# ink2.net
KiCad netlist of a schematic drawn in EAGLE
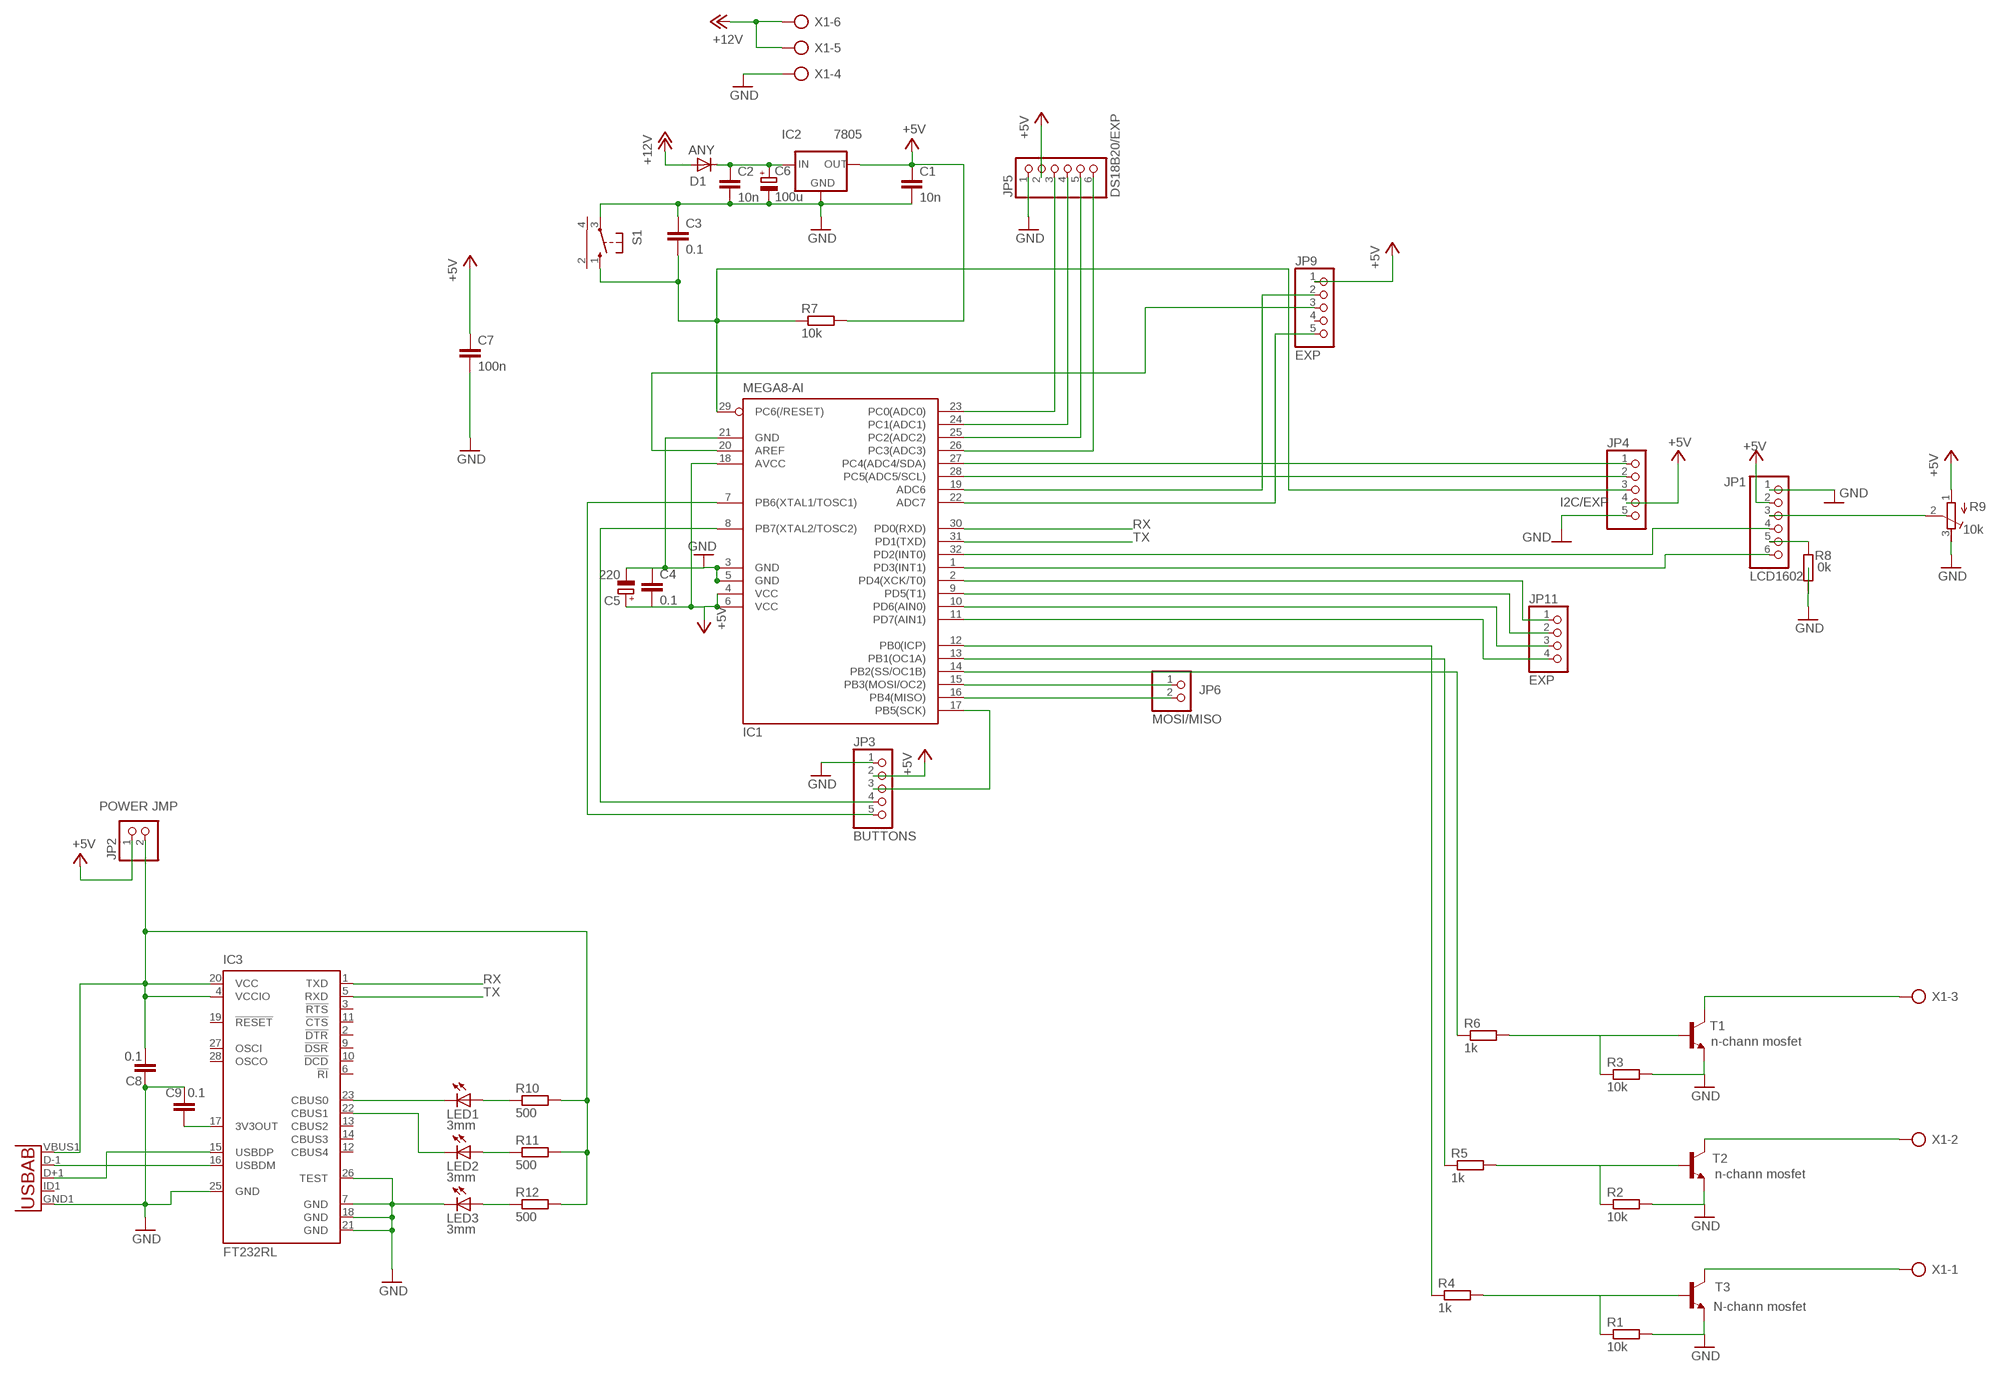
[diagram p0: schematic, sheet 1]

(export (version "E")
  (design (tool "Eeschema 10.0.6"))
  (components
    (comp (ref "ANY")
      (value "D1")
      (footprint "eagle-import:SOD-123_MINI-SMA")
      (libsource (lib "eagle-import") (part "CGRM400-G1"))
    )
    (comp (ref "C1")
      (value "10n")
      (footprint "eagle-import:C1206")
      (libsource (lib "eagle-import") (part "C-EUC1206"))
    )
    (comp (ref "C2")
      (value "10n")
      (footprint "eagle-import:C1206")
      (libsource (lib "eagle-import") (part "C-EUC1206"))
    )
    (comp (ref "C3")
      (value "0.1")
      (footprint "eagle-import:C1206")
      (libsource (lib "eagle-import") (part "C-EUC1206"))
    )
    (comp (ref "C4")
      (value "0.1")
      (footprint "eagle-import:C1206")
      (libsource (lib "eagle-import") (part "C-EUC1206"))
    )
    (comp (ref "C5")
      (value "220")
      (footprint "eagle-import:175TMP-0808")
      (libsource (lib "eagle-import") (part "CPOL-EU175TMP-0808"))
    )
    (comp (ref "C6")
      (value "100u")
      (footprint "eagle-import:140CLH-1010")
      (libsource (lib "eagle-import") (part "CPOL-EU140CLH-1010"))
    )
    (comp (ref "C7")
      (value "100n")
      (footprint "eagle-import:C1206K")
      (libsource (lib "eagle-import") (part "C-EUC1206K"))
    )
    (comp (ref "C8")
      (value "0.1")
      (footprint "eagle-import:C1206")
      (libsource (lib "eagle-import") (part "C-EUC1206"))
    )
    (comp (ref "C9")
      (value "0.1")
      (footprint "eagle-import:C1206")
      (libsource (lib "eagle-import") (part "C-EUC1206"))
    )
    (comp (ref "IC1")
      (value "MEGA8-AI")
      (footprint "eagle-import:TQFP32-08")
      (fields (field (name "MPN") "ATMEGA8-16AU"))
      (libsource (lib "eagle-import") (part "MEGA8-AI"))
    )
    (comp (ref "IC2")
      (value "7805")
      (footprint "eagle-import:DPACK")
      (libsource (lib "eagle-import") (part "78MXXLDP"))
    )
    (comp (ref "IC3")
      (value "FT232RL")
      (footprint "eagle-import:SSOP28")
      (libsource (lib "eagle-import") (part "FT232RL"))
    )
    (comp (ref "JP1")
      (value "LCD1602")
      (footprint "eagle-import:1X06")
      (libsource (lib "eagle-import") (part "PINHD-1X6"))
    )
    (comp (ref "JP2")
      (value "POWER JMP")
      (footprint "eagle-import:1X02")
      (libsource (lib "eagle-import") (part "PINHD-1X2"))
    )
    (comp (ref "JP3")
      (value "BUTTONS")
      (footprint "eagle-import:1X05")
      (libsource (lib "eagle-import") (part "PINHD-1X5"))
    )
    (comp (ref "JP4")
      (value "I2C/EXP")
      (footprint "eagle-import:1X05")
      (libsource (lib "eagle-import") (part "PINHD-1X5"))
    )
    (comp (ref "JP5")
      (value "DS18B20/EXP")
      (footprint "eagle-import:1X06")
      (libsource (lib "eagle-import") (part "PINHD-1X6"))
    )
    (comp (ref "JP6")
      (value "MOSI/MISO")
      (footprint "eagle-import:1X02")
      (libsource (lib "eagle-import") (part "PINHD-1X2"))
    )
    (comp (ref "JP9")
      (value "EXP")
      (footprint "eagle-import:1X05")
      (libsource (lib "eagle-import") (part "PINHD-1X5"))
    )
    (comp (ref "JP11")
      (value "EXP")
      (footprint "eagle-import:1X04")
      (libsource (lib "eagle-import") (part "PINHD-1X4"))
    )
    (comp (ref "LED1")
      (value "3mm")
      (footprint "eagle-import:LED3MM")
      (libsource (lib "eagle-import") (part "LED3MM"))
    )
    (comp (ref "LED2")
      (value "3mm")
      (footprint "eagle-import:LED3MM")
      (libsource (lib "eagle-import") (part "LED3MM"))
    )
    (comp (ref "LED3")
      (value "3mm")
      (footprint "eagle-import:LED3MM")
      (libsource (lib "eagle-import") (part "LED3MM"))
    )
    (comp (ref "R1")
      (value "10k")
      (footprint "eagle-import:M1206")
      (libsource (lib "eagle-import") (part "resistor_R-EU_M1206"))
    )
    (comp (ref "R2")
      (value "10k")
      (footprint "eagle-import:M1206")
      (libsource (lib "eagle-import") (part "resistor_R-EU_M1206"))
    )
    (comp (ref "R3")
      (value "10k")
      (footprint "eagle-import:M1206")
      (libsource (lib "eagle-import") (part "resistor_R-EU_M1206"))
    )
    (comp (ref "R4")
      (value "1k")
      (footprint "eagle-import:M1206")
      (libsource (lib "eagle-import") (part "resistor_R-EU_M1206"))
    )
    (comp (ref "R5")
      (value "1k")
      (footprint "eagle-import:M1206")
      (libsource (lib "eagle-import") (part "resistor_R-EU_M1206"))
    )
    (comp (ref "R6")
      (value "1k")
      (footprint "eagle-import:M1206")
      (libsource (lib "eagle-import") (part "resistor_R-EU_M1206"))
    )
    (comp (ref "R7")
      (value "10k")
      (footprint "eagle-import:M1206")
      (libsource (lib "eagle-import") (part "resistor_R-EU_M1206"))
    )
    (comp (ref "R8")
      (value "0k")
      (footprint "eagle-import:M1206")
      (libsource (lib "eagle-import") (part "R-EU_M1206"))
    )
    (comp (ref "R9")
      (value "10k")
      (footprint "eagle-import:RTRIM64Y")
      (libsource (lib "eagle-import") (part "R-TRIMM64Y"))
    )
    (comp (ref "R10")
      (value "500")
      (footprint "eagle-import:M1206")
      (libsource (lib "eagle-import") (part "resistor_R-EU_M1206"))
    )
    (comp (ref "R11")
      (value "500")
      (footprint "eagle-import:M1206")
      (libsource (lib "eagle-import") (part "resistor_R-EU_M1206"))
    )
    (comp (ref "R12")
      (value "500")
      (footprint "eagle-import:M1206")
      (libsource (lib "eagle-import") (part "resistor_R-EU_M1206"))
    )
    (comp (ref "S1")
      (value "10-XX-RPAD")
      (footprint "eagle-import:B3F-10XX-RPAD")
      (libsource (lib "eagle-import") (part "10-XX-RPAD"))
    )
    (comp (ref "T1")
      (value "n-chann mosfet")
      (footprint "eagle-import:DPAK")
      (libsource (lib "eagle-import") (part "MJD31"))
    )
    (comp (ref "T2")
      (value "n-chann mosfet")
      (footprint "eagle-import:DPAK")
      (libsource (lib "eagle-import") (part "MJD31"))
    )
    (comp (ref "T3")
      (value "N-chann mosfet")
      (footprint "eagle-import:DPAK")
      (libsource (lib "eagle-import") (part "MJD31"))
    )
    (comp (ref "U1")
      (value "USB\"\"")
      (footprint "eagle-import:USB-MICRO-SMD")
      (libsource (lib "eagle-import") (part "USB{dblquote}{dblquote}"))
    )
    (comp (ref "X1")
      (value "AK300/6")
      (footprint "eagle-import:AK300_6")
      (libsource (lib "eagle-import") (part "AK300/6"))
    )
  )
  (nets
    (net (code "1") (name "+5V") (class "Default")
      (node (ref "C1") (pin "1") (pinfunction "1_1") (pintype "passive"))
      (node (ref "C4") (pin "2") (pinfunction "2_2") (pintype "passive"))
      (node (ref "C5") (pin "+") (pinfunction "+_+") (pintype "passive"))
      (node (ref "C7") (pin "1") (pinfunction "1_1") (pintype "passive"))
      (node (ref "IC1") (pin "18") (pinfunction "AVCC_18") (pintype "power_in"))
      (node (ref "IC1") (pin "4") (pinfunction "VCC_4") (pintype "power_in"))
      (node (ref "IC1") (pin "6") (pinfunction "VCC_6") (pintype "power_in"))
      (node (ref "IC2") (pin "3") (pinfunction "OUT_3") (pintype "passive"))
      (node (ref "JP1") (pin "2") (pinfunction "2_2") (pintype "passive"))
      (node (ref "JP2") (pin "1") (pinfunction "1_1") (pintype "passive"))
      (node (ref "JP3") (pin "2") (pinfunction "2_2") (pintype "passive"))
      (node (ref "JP4") (pin "4") (pinfunction "4_4") (pintype "passive"))
      (node (ref "JP5") (pin "2") (pinfunction "2_2") (pintype "passive"))
      (node (ref "JP9") (pin "1") (pinfunction "1_1") (pintype "passive"))
      (node (ref "R7") (pin "2") (pinfunction "2_2") (pintype "passive"))
      (node (ref "R9") (pin "1") (pinfunction "A_1") (pintype "passive"))
    )
    (net (code "2") (name "+12V") (class "Default")
      (node (ref "ANY") (pin "A") (pinfunction "A_A") (pintype "passive"))
      (node (ref "X1") (pin "5") (pinfunction "KL_5") (pintype "passive"))
      (node (ref "X1") (pin "6") (pinfunction "KL_6") (pintype "passive"))
    )
    (net (code "3") (name "/RX") (class "Default")
      (node (ref "IC1") (pin "30") (pinfunction "PD0(RXD)_30") (pintype "bidirectional"))
      (node (ref "IC3") (pin "1") (pinfunction "TXD_1") (pintype "output"))
    )
    (net (code "4") (name "/TX") (class "Default")
      (node (ref "IC1") (pin "31") (pinfunction "PD1(TXD)_31") (pintype "bidirectional"))
      (node (ref "IC3") (pin "5") (pinfunction "RXD_5") (pintype "input"))
    )
    (net (code "5") (name "GND") (class "Default")
      (node (ref "C1") (pin "2") (pinfunction "2_2") (pintype "passive"))
      (node (ref "C2") (pin "2") (pinfunction "2_2") (pintype "passive"))
      (node (ref "C3") (pin "1") (pinfunction "1_1") (pintype "passive"))
      (node (ref "C4") (pin "1") (pinfunction "1_1") (pintype "passive"))
      (node (ref "C5") (pin "-") (pinfunction "-_-") (pintype "passive"))
      (node (ref "C6") (pin "-") (pinfunction "-_-") (pintype "passive"))
      (node (ref "C7") (pin "2") (pinfunction "2_2") (pintype "passive"))
      (node (ref "C8") (pin "2") (pinfunction "2_2") (pintype "passive"))
      (node (ref "C9") (pin "2") (pinfunction "2_2") (pintype "passive"))
      (node (ref "IC1") (pin "21") (pinfunction "GND_21") (pintype "power_in"))
      (node (ref "IC1") (pin "3") (pinfunction "GND_3") (pintype "power_in"))
      (node (ref "IC1") (pin "5") (pinfunction "GND_5") (pintype "power_in"))
      (node (ref "IC2") (pin "4") (pinfunction "GND_4") (pintype "input"))
      (node (ref "IC3") (pin "18") (pinfunction "GND_18") (pintype "power_in"))
      (node (ref "IC3") (pin "21") (pinfunction "GND_21") (pintype "power_in"))
      (node (ref "IC3") (pin "25") (pinfunction "GND_25") (pintype "power_in"))
      (node (ref "IC3") (pin "26") (pinfunction "TEST_26") (pintype "input"))
      (node (ref "IC3") (pin "7") (pinfunction "GND_7") (pintype "power_in"))
      (node (ref "JP1") (pin "1") (pinfunction "1_1") (pintype "passive"))
      (node (ref "JP3") (pin "1") (pinfunction "1_1") (pintype "passive"))
      (node (ref "JP4") (pin "5") (pinfunction "5_5") (pintype "passive"))
      (node (ref "JP5") (pin "1") (pinfunction "1_1") (pintype "passive"))
      (node (ref "LED3") (pin "K") (pinfunction "C_K") (pintype "passive"))
      (node (ref "R1") (pin "2") (pinfunction "2_2") (pintype "passive"))
      (node (ref "R2") (pin "2") (pinfunction "2_2") (pintype "passive"))
      (node (ref "R3") (pin "2") (pinfunction "2_2") (pintype "passive"))
      (node (ref "R8") (pin "2") (pinfunction "2_2") (pintype "passive"))
      (node (ref "R9") (pin "3") (pinfunction "E_3") (pintype "passive"))
      (node (ref "S1") (pin "3") (pinfunction "P_3") (pintype "passive"))
      (node (ref "T1") (pin "3") (pinfunction "E_3") (pintype "passive"))
      (node (ref "T2") (pin "3") (pinfunction "E_3") (pintype "passive"))
      (node (ref "T3") (pin "3") (pinfunction "E_3") (pintype "passive"))
      (node (ref "U1") (pin "GND1") (pinfunction "GND_GND1") (pintype "bidirectional"))
      (node (ref "X1") (pin "4") (pinfunction "KL_4") (pintype "passive"))
    )
    (net (code "6") (name "Net-(IC1-ADC6)") (class "Default")
      (node (ref "IC1") (pin "19") (pinfunction "ADC6_19") (pintype "bidirectional"))
      (node (ref "JP9") (pin "2") (pinfunction "2_2") (pintype "passive"))
    )
    (net (code "7") (name "Net-(IC1-ADC7)") (class "Default")
      (node (ref "IC1") (pin "22") (pinfunction "ADC7_22") (pintype "bidirectional"))
      (node (ref "JP9") (pin "5") (pinfunction "5_5") (pintype "passive"))
    )
    (net (code "8") (name "Net-(IC1-AREF)") (class "Default")
      (node (ref "IC1") (pin "20") (pinfunction "AREF_20") (pintype "passive"))
      (node (ref "JP9") (pin "3") (pinfunction "3_3") (pintype "passive"))
    )
    (net (code "9") (name "Net-(IC1-PB0(ICP))") (class "Default")
      (node (ref "IC1") (pin "12") (pinfunction "PB0(ICP)_12") (pintype "bidirectional"))
      (node (ref "R4") (pin "1") (pinfunction "1_1") (pintype "passive"))
    )
    (net (code "10") (name "Net-(IC1-PB1(OC1A))") (class "Default")
      (node (ref "IC1") (pin "13") (pinfunction "PB1(OC1A)_13") (pintype "bidirectional"))
      (node (ref "R5") (pin "1") (pinfunction "1_1") (pintype "passive"))
    )
    (net (code "11") (name "Net-(IC1-PB2(SS{slash}OC1B))") (class "Default")
      (node (ref "IC1") (pin "14") (pinfunction "PB2(SS/OC1B)_14") (pintype "bidirectional"))
      (node (ref "R6") (pin "1") (pinfunction "1_1") (pintype "passive"))
    )
    (net (code "12") (name "Net-(IC1-PB3(MOSI{slash}OC2))") (class "Default")
      (node (ref "IC1") (pin "15") (pinfunction "PB3(MOSI/OC2)_15") (pintype "bidirectional"))
      (node (ref "JP6") (pin "1") (pinfunction "1_1") (pintype "passive"))
    )
    (net (code "13") (name "Net-(IC1-PB4(MISO))") (class "Default")
      (node (ref "IC1") (pin "16") (pinfunction "PB4(MISO)_16") (pintype "bidirectional"))
      (node (ref "JP6") (pin "2") (pinfunction "2_2") (pintype "passive"))
    )
    (net (code "14") (name "Net-(IC1-PB5(SCK))") (class "Default")
      (node (ref "IC1") (pin "17") (pinfunction "PB5(SCK)_17") (pintype "bidirectional"))
      (node (ref "JP3") (pin "3") (pinfunction "3_3") (pintype "passive"))
    )
    (net (code "15") (name "Net-(IC1-PB6(XTAL1{slash}TOSC1))") (class "Default")
      (node (ref "IC1") (pin "7") (pinfunction "PB6(XTAL1/TOSC1)_7") (pintype "bidirectional"))
      (node (ref "JP3") (pin "5") (pinfunction "5_5") (pintype "passive"))
    )
    (net (code "16") (name "Net-(IC1-PB7(XTAL2{slash}TOSC2))") (class "Default")
      (node (ref "IC1") (pin "8") (pinfunction "PB7(XTAL2/TOSC2)_8") (pintype "bidirectional"))
      (node (ref "JP3") (pin "4") (pinfunction "4_4") (pintype "passive"))
    )
    (net (code "17") (name "Net-(IC1-PC0(ADC0))") (class "Default")
      (node (ref "IC1") (pin "23") (pinfunction "PC0(ADC0)_23") (pintype "bidirectional"))
      (node (ref "JP5") (pin "3") (pinfunction "3_3") (pintype "passive"))
    )
    (net (code "18") (name "Net-(IC1-PC1(ADC1))") (class "Default")
      (node (ref "IC1") (pin "24") (pinfunction "PC1(ADC1)_24") (pintype "bidirectional"))
      (node (ref "JP5") (pin "4") (pinfunction "4_4") (pintype "passive"))
    )
    (net (code "19") (name "Net-(IC1-PC2(ADC2))") (class "Default")
      (node (ref "IC1") (pin "25") (pinfunction "PC2(ADC2)_25") (pintype "bidirectional"))
      (node (ref "JP5") (pin "5") (pinfunction "5_5") (pintype "passive"))
    )
    (net (code "20") (name "Net-(IC1-PC3(ADC3))") (class "Default")
      (node (ref "IC1") (pin "26") (pinfunction "PC3(ADC3)_26") (pintype "bidirectional"))
      (node (ref "JP5") (pin "6") (pinfunction "6_6") (pintype "passive"))
    )
    (net (code "21") (name "Net-(IC1-PC4(ADC4{slash}SDA))") (class "Default")
      (node (ref "IC1") (pin "27") (pinfunction "PC4(ADC4/SDA)_27") (pintype "bidirectional"))
      (node (ref "JP4") (pin "1") (pinfunction "1_1") (pintype "passive"))
    )
    (net (code "22") (name "Net-(IC1-PC5(ADC5{slash}SCL))") (class "Default")
      (node (ref "IC1") (pin "28") (pinfunction "PC5(ADC5/SCL)_28") (pintype "bidirectional"))
      (node (ref "JP4") (pin "2") (pinfunction "2_2") (pintype "passive"))
    )
    (net (code "23") (name "Net-(IC1-PC6({slash}RESET))") (class "Default")
      (node (ref "C3") (pin "2") (pinfunction "2_2") (pintype "passive"))
      (node (ref "IC1") (pin "29") (pinfunction "PC6(/RESET)_29") (pintype "bidirectional"))
      (node (ref "JP4") (pin "3") (pinfunction "3_3") (pintype "passive"))
      (node (ref "R7") (pin "1") (pinfunction "1_1") (pintype "passive"))
      (node (ref "S1") (pin "1") (pinfunction "S_1") (pintype "passive"))
    )
    (net (code "24") (name "Net-(IC1-PD2(INT0))") (class "Default")
      (node (ref "IC1") (pin "32") (pinfunction "PD2(INT0)_32") (pintype "bidirectional"))
      (node (ref "JP1") (pin "4") (pinfunction "4_4") (pintype "passive"))
    )
    (net (code "25") (name "Net-(IC1-PD3(INT1))") (class "Default")
      (node (ref "IC1") (pin "1") (pinfunction "PD3(INT1)_1") (pintype "bidirectional"))
      (node (ref "JP1") (pin "6") (pinfunction "6_6") (pintype "passive"))
    )
    (net (code "26") (name "Net-(IC1-PD4(XCK{slash}T0))") (class "Default")
      (node (ref "IC1") (pin "2") (pinfunction "PD4(XCK/T0)_2") (pintype "bidirectional"))
      (node (ref "JP11") (pin "1") (pinfunction "1_1") (pintype "passive"))
    )
    (net (code "27") (name "Net-(IC1-PD5(T1))") (class "Default")
      (node (ref "IC1") (pin "9") (pinfunction "PD5(T1)_9") (pintype "bidirectional"))
      (node (ref "JP11") (pin "2") (pinfunction "2_2") (pintype "passive"))
    )
    (net (code "28") (name "Net-(IC1-PD6(AIN0))") (class "Default")
      (node (ref "IC1") (pin "10") (pinfunction "PD6(AIN0)_10") (pintype "bidirectional"))
      (node (ref "JP11") (pin "3") (pinfunction "3_3") (pintype "passive"))
    )
    (net (code "29") (name "Net-(IC1-PD7(AIN1))") (class "Default")
      (node (ref "IC1") (pin "11") (pinfunction "PD7(AIN1)_11") (pintype "bidirectional"))
      (node (ref "JP11") (pin "4") (pinfunction "4_4") (pintype "passive"))
    )
    (net (code "30") (name "Net-(IC2-IN)") (class "Default")
      (node (ref "ANY") (pin "C") (pinfunction "C_C") (pintype "passive"))
      (node (ref "C2") (pin "1") (pinfunction "1_1") (pintype "passive"))
      (node (ref "C6") (pin "+") (pinfunction "+_+") (pintype "passive"))
      (node (ref "IC2") (pin "1") (pinfunction "IN_1") (pintype "input"))
    )
    (net (code "31") (name "Net-(IC3-3V3OUT)") (class "Default")
      (node (ref "C9") (pin "1") (pinfunction "1_1") (pintype "passive"))
      (node (ref "IC3") (pin "17") (pinfunction "3V3OUT_17") (pintype "output"))
    )
    (net (code "32") (name "Net-(IC3-CBUS0)") (class "Default")
      (node (ref "IC3") (pin "23") (pinfunction "CBUS0_23") (pintype "bidirectional"))
      (node (ref "LED1") (pin "K") (pinfunction "C_K") (pintype "passive"))
    )
    (net (code "33") (name "Net-(IC3-CBUS1)") (class "Default")
      (node (ref "IC3") (pin "22") (pinfunction "CBUS1_22") (pintype "bidirectional"))
      (node (ref "LED2") (pin "K") (pinfunction "C_K") (pintype "passive"))
    )
    (net (code "34") (name "Net-(IC3-USBDM)") (class "Default")
      (node (ref "IC3") (pin "16") (pinfunction "USBDM_16") (pintype "bidirectional"))
      (node (ref "U1") (pin "D-1") (pinfunction "D-_D-1") (pintype "bidirectional"))
    )
    (net (code "35") (name "Net-(IC3-USBDP)") (class "Default")
      (node (ref "IC3") (pin "15") (pinfunction "USBDP_15") (pintype "bidirectional"))
      (node (ref "U1") (pin "D+1") (pinfunction "D+_D+1") (pintype "bidirectional"))
    )
    (net (code "36") (name "Net-(IC3-VCC)") (class "Default")
      (node (ref "C8") (pin "1") (pinfunction "1_1") (pintype "passive"))
      (node (ref "IC3") (pin "20") (pinfunction "VCC_20") (pintype "power_in"))
      (node (ref "IC3") (pin "4") (pinfunction "VCCIO_4") (pintype "power_in"))
      (node (ref "JP2") (pin "2") (pinfunction "2_2") (pintype "passive"))
      (node (ref "R10") (pin "2") (pinfunction "2_2") (pintype "passive"))
      (node (ref "R11") (pin "2") (pinfunction "2_2") (pintype "passive"))
      (node (ref "R12") (pin "2") (pinfunction "2_2") (pintype "passive"))
      (node (ref "U1") (pin "VBUS1") (pinfunction "VBUS_VBUS1") (pintype "bidirectional"))
    )
    (net (code "37") (name "Net-(JP1-Pad5)") (class "Default")
      (node (ref "JP1") (pin "5") (pinfunction "5_5") (pintype "passive"))
      (node (ref "R8") (pin "1") (pinfunction "1_1") (pintype "passive"))
    )
    (net (code "38") (name "Net-(LED1-PadA)") (class "Default")
      (node (ref "LED1") (pin "A") (pinfunction "A_A") (pintype "passive"))
      (node (ref "R10") (pin "1") (pinfunction "1_1") (pintype "passive"))
    )
    (net (code "39") (name "Net-(LED2-PadA)") (class "Default")
      (node (ref "LED2") (pin "A") (pinfunction "A_A") (pintype "passive"))
      (node (ref "R11") (pin "1") (pinfunction "1_1") (pintype "passive"))
    )
    (net (code "40") (name "Net-(LED3-PadA)") (class "Default")
      (node (ref "LED3") (pin "A") (pinfunction "A_A") (pintype "passive"))
      (node (ref "R12") (pin "1") (pinfunction "1_1") (pintype "passive"))
    )
    (net (code "41") (name "Net-(R9-S)") (class "Default")
      (node (ref "JP1") (pin "3") (pinfunction "3_3") (pintype "passive"))
      (node (ref "R9") (pin "2") (pinfunction "S_2") (pintype "passive"))
    )
    (net (code "42") (name "Net-(T1-B)") (class "Default")
      (node (ref "R3") (pin "1") (pinfunction "1_1") (pintype "passive"))
      (node (ref "R6") (pin "2") (pinfunction "2_2") (pintype "passive"))
      (node (ref "T1") (pin "1") (pinfunction "B_1") (pintype "passive"))
    )
    (net (code "43") (name "Net-(T1-C)") (class "Default")
      (node (ref "T1") (pin "4") (pinfunction "C_4") (pintype "passive"))
      (node (ref "X1") (pin "3") (pinfunction "KL_3") (pintype "passive"))
    )
    (net (code "44") (name "Net-(T2-B)") (class "Default")
      (node (ref "R2") (pin "1") (pinfunction "1_1") (pintype "passive"))
      (node (ref "R5") (pin "2") (pinfunction "2_2") (pintype "passive"))
      (node (ref "T2") (pin "1") (pinfunction "B_1") (pintype "passive"))
    )
    (net (code "45") (name "Net-(T2-C)") (class "Default")
      (node (ref "T2") (pin "4") (pinfunction "C_4") (pintype "passive"))
      (node (ref "X1") (pin "2") (pinfunction "KL_2") (pintype "passive"))
    )
    (net (code "46") (name "Net-(T3-B)") (class "Default")
      (node (ref "R1") (pin "1") (pinfunction "1_1") (pintype "passive"))
      (node (ref "R4") (pin "2") (pinfunction "2_2") (pintype "passive"))
      (node (ref "T3") (pin "1") (pinfunction "B_1") (pintype "passive"))
    )
    (net (code "47") (name "Net-(T3-C)") (class "Default")
      (node (ref "T3") (pin "4") (pinfunction "C_4") (pintype "passive"))
      (node (ref "X1") (pin "1") (pinfunction "KL_1") (pintype "passive"))
    )
    (net (code "48") (name "unconnected-(IC3-CBUS2-Pad13)") (class "Default")
      (node (ref "IC3") (pin "13") (pinfunction "CBUS2_13") (pintype "bidirectional"))
    )
    (net (code "49") (name "unconnected-(IC3-CBUS3-Pad14)") (class "Default")
      (node (ref "IC3") (pin "14") (pinfunction "CBUS3_14") (pintype "bidirectional"))
    )
    (net (code "50") (name "unconnected-(IC3-CBUS4-Pad12)") (class "Default")
      (node (ref "IC3") (pin "12") (pinfunction "CBUS4_12") (pintype "bidirectional"))
    )
    (net (code "51") (name "unconnected-(IC3-OSCI-Pad27)") (class "Default")
      (node (ref "IC3") (pin "27") (pinfunction "OSCI_27") (pintype "input"))
    )
    (net (code "52") (name "unconnected-(IC3-OSCO-Pad28)") (class "Default")
      (node (ref "IC3") (pin "28") (pinfunction "OSCO_28") (pintype "output"))
    )
    (net (code "53") (name "unconnected-(IC3-~{CTS}-Pad11)") (class "Default")
      (node (ref "IC3") (pin "11") (pinfunction "~{CTS}_11") (pintype "input"))
    )
    (net (code "54") (name "unconnected-(IC3-~{DCD}-Pad10)") (class "Default")
      (node (ref "IC3") (pin "10") (pinfunction "~{DCD}_10") (pintype "input"))
    )
    (net (code "55") (name "unconnected-(IC3-~{DSR}-Pad9)") (class "Default")
      (node (ref "IC3") (pin "9") (pinfunction "~{DSR}_9") (pintype "input"))
    )
    (net (code "56") (name "unconnected-(IC3-~{DTR}-Pad2)") (class "Default")
      (node (ref "IC3") (pin "2") (pinfunction "~{DTR}_2") (pintype "output"))
    )
    (net (code "57") (name "unconnected-(IC3-~{RESET}-Pad19)") (class "Default")
      (node (ref "IC3") (pin "19") (pinfunction "~{RESET}_19") (pintype "input"))
    )
    (net (code "58") (name "unconnected-(IC3-~{RI}-Pad6)") (class "Default")
      (node (ref "IC3") (pin "6") (pinfunction "~{RI}_6") (pintype "input"))
    )
    (net (code "59") (name "unconnected-(IC3-~{RTS}-Pad3)") (class "Default")
      (node (ref "IC3") (pin "3") (pinfunction "~{RTS}_3") (pintype "output"))
    )
    (net (code "60") (name "unconnected-(JP9-Pad4)") (class "Default")
      (node (ref "JP9") (pin "4") (pinfunction "4_4") (pintype "passive"))
    )
    (net (code "61") (name "unconnected-(S1-GND1-Pad2)") (class "Default")
      (node (ref "S1") (pin "2") (pinfunction "GND1_2") (pintype "passive"))
    )
    (net (code "62") (name "unconnected-(S1-GND2-Pad4)") (class "Default")
      (node (ref "S1") (pin "4") (pinfunction "GND2_4") (pintype "passive"))
    )
    (net (code "63") (name "unconnected-(U1-USBID-PadID1)") (class "Default")
      (node (ref "U1") (pin "ID1") (pinfunction "USBID_ID1") (pintype "bidirectional"))
    )
  )
)
